# WaldoRevB.net
KiCad netlist of a schematic drawn in EAGLE
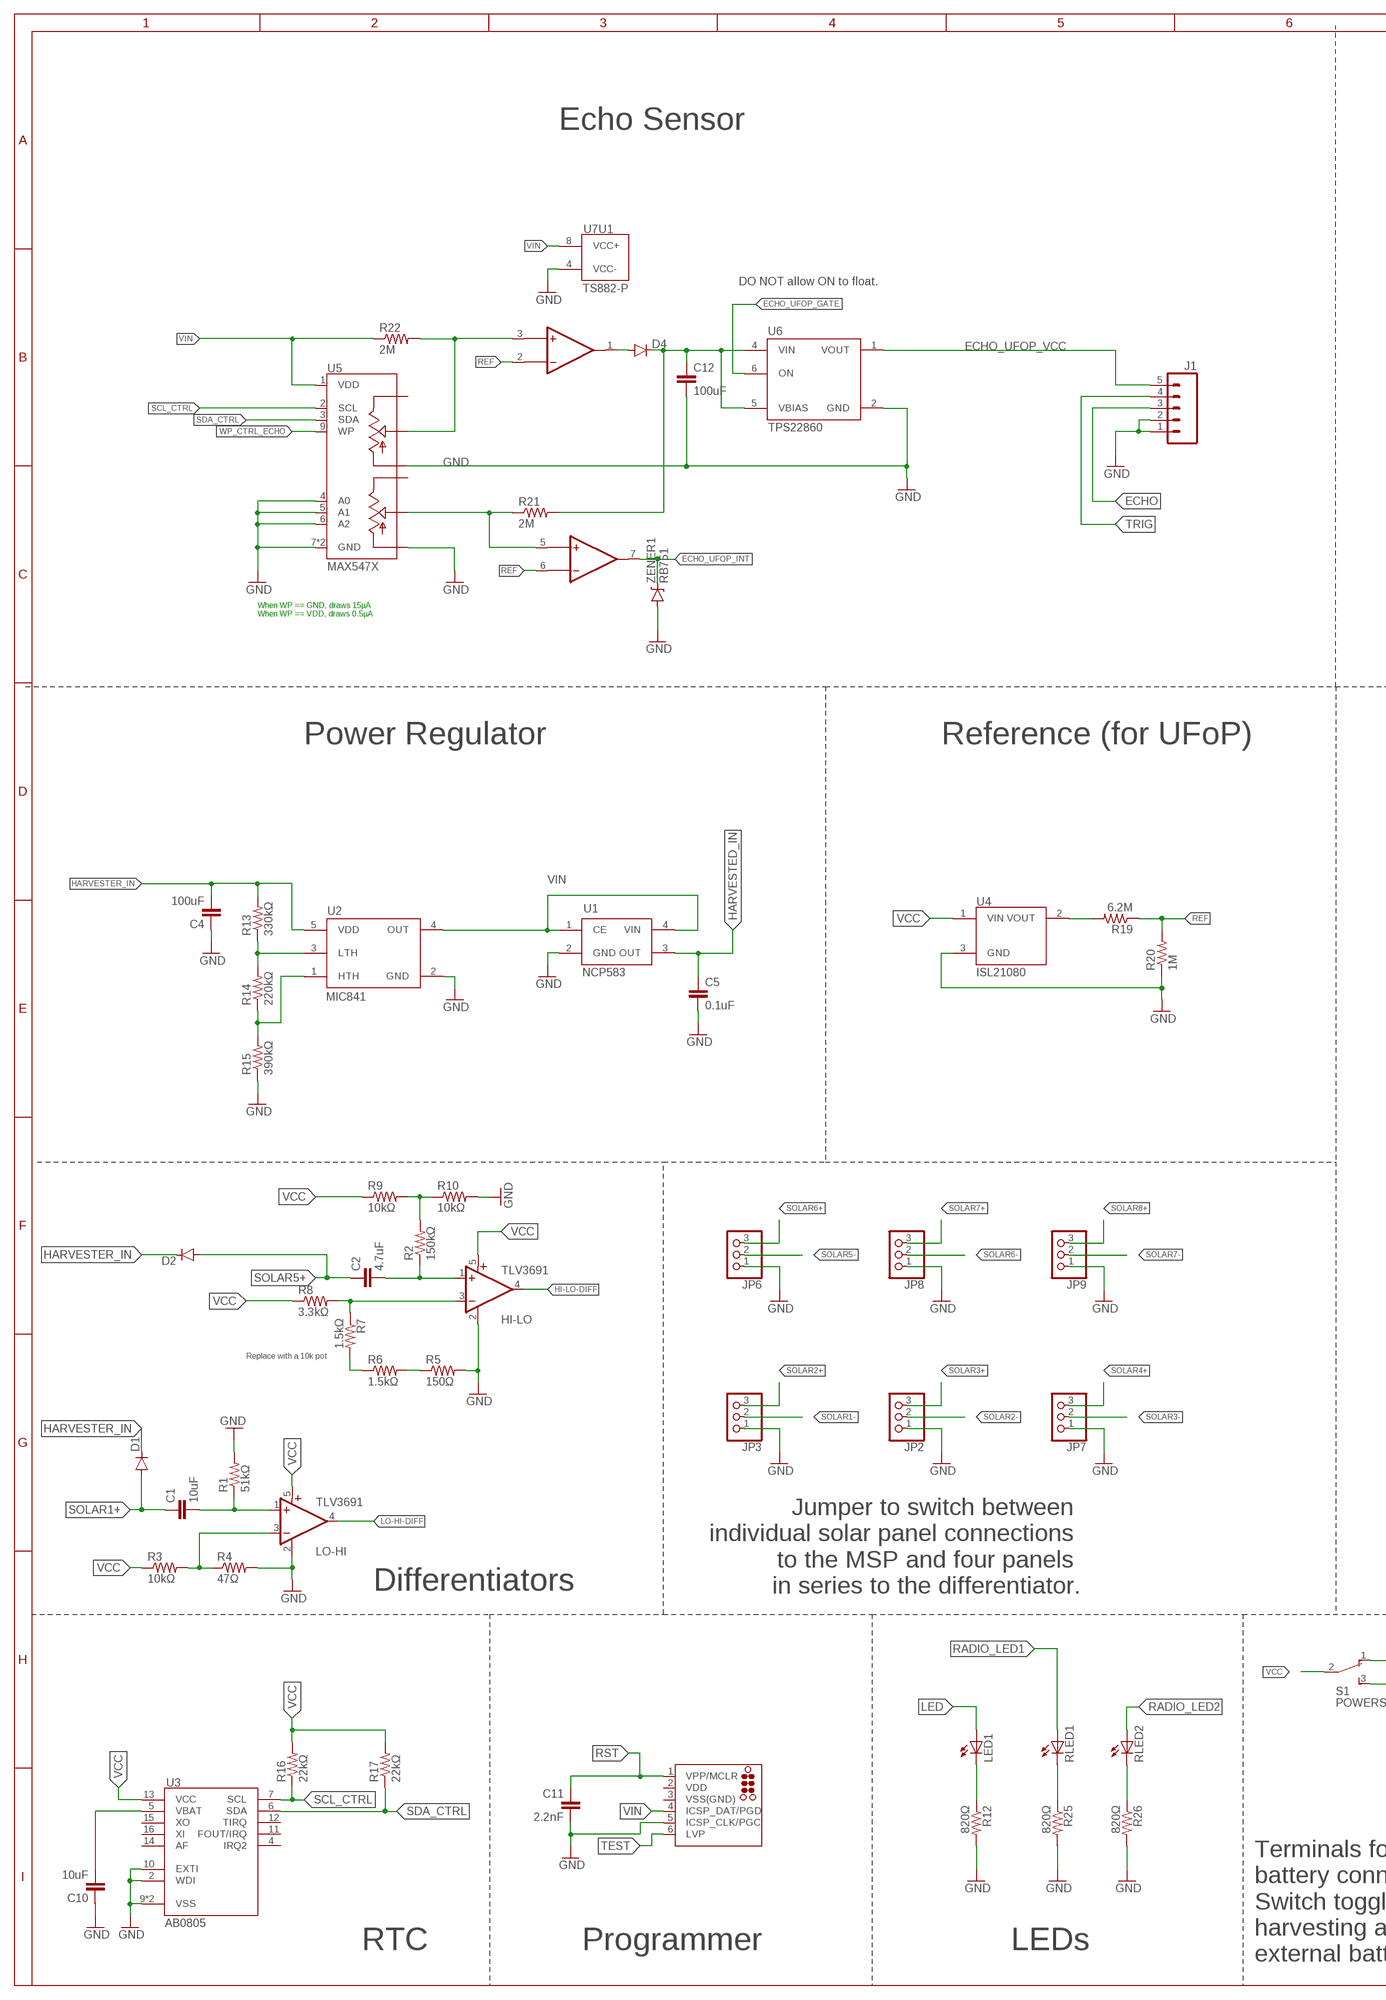
[diagram p0: schematic, sheet 1, part 1 of 2]
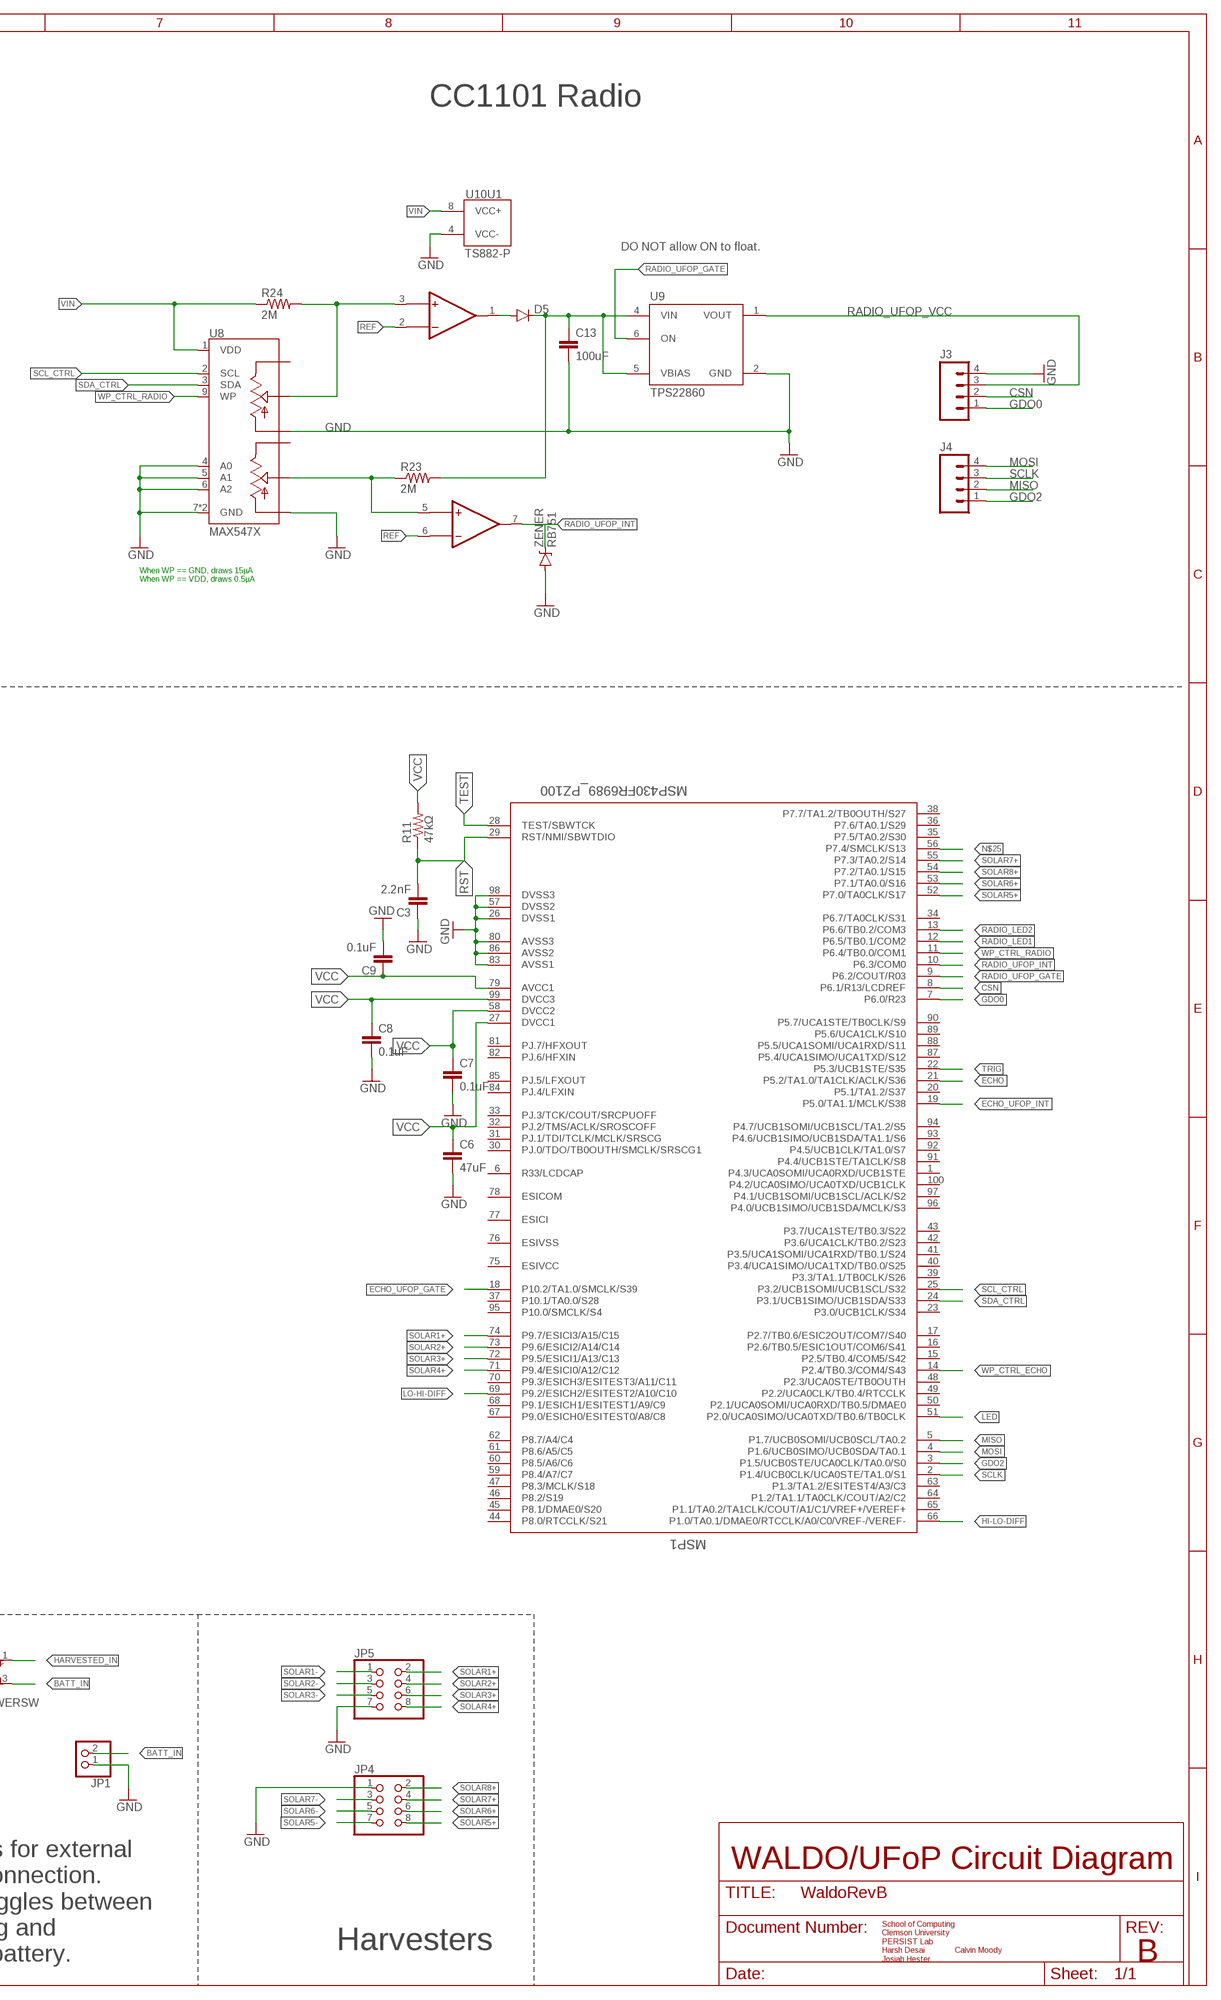
[diagram p1: schematic, sheet 1, part 2 of 2]

(export (version "E")
  (design (tool "Eeschema 10.0.6"))
  (components
    (comp (ref "C1")
      (value "10uF")
      (footprint "eagle-import:0805")
      (libsource (lib "eagle-import") (part "CAP0805"))
    )
    (comp (ref "C2")
      (value "4.7uF")
      (footprint "eagle-import:0805")
      (libsource (lib "eagle-import") (part "CAP0805"))
    )
    (comp (ref "C3")
      (value "2.2nF")
      (footprint "eagle-import:0805")
      (libsource (lib "eagle-import") (part "CAP0805"))
    )
    (comp (ref "C4")
      (value "100uF")
      (footprint "eagle-import:0805")
      (libsource (lib "eagle-import") (part "CAP0805"))
    )
    (comp (ref "C5")
      (value "0.1uF")
      (footprint "eagle-import:0805")
      (libsource (lib "eagle-import") (part "CAP0805"))
    )
    (comp (ref "C6")
      (value "47uF")
      (footprint "eagle-import:0805")
      (libsource (lib "eagle-import") (part "CAP0805"))
    )
    (comp (ref "C7")
      (value "0.1uF")
      (footprint "eagle-import:0805")
      (libsource (lib "eagle-import") (part "CAP0805"))
    )
    (comp (ref "C8")
      (value "0.1uF")
      (footprint "eagle-import:0805")
      (libsource (lib "eagle-import") (part "CAP0805"))
    )
    (comp (ref "C9")
      (value "0.1uF")
      (footprint "eagle-import:0805")
      (libsource (lib "eagle-import") (part "CAP0805"))
    )
    (comp (ref "C10")
      (value "10uF")
      (footprint "eagle-import:0805")
      (libsource (lib "eagle-import") (part "CAP0805"))
    )
    (comp (ref "C11")
      (value "2.2nF")
      (footprint "eagle-import:0805")
      (libsource (lib "eagle-import") (part "CAP0805"))
    )
    (comp (ref "C12")
      (value "100uF")
      (footprint "eagle-import:0805")
      (libsource (lib "eagle-import") (part "CAP0805"))
    )
    (comp (ref "C13")
      (value "100uF")
      (footprint "eagle-import:0805")
      (libsource (lib "eagle-import") (part "CAP0805"))
    )
    (comp (ref "D1")
      (value "DIODESOD523")
      (footprint "eagle-import:SOD523")
      (libsource (lib "eagle-import") (part "DIODESOD523"))
    )
    (comp (ref "D2")
      (value "DIODESOD523")
      (footprint "eagle-import:SOD523")
      (libsource (lib "eagle-import") (part "DIODESOD523"))
    )
    (comp (ref "D4")
      (value "DIODESOD523")
      (footprint "eagle-import:SOD523")
      (libsource (lib "eagle-import") (part "DIODESOD523"))
    )
    (comp (ref "D5")
      (value "DIODESOD523")
      (footprint "eagle-import:SOD523")
      (libsource (lib "eagle-import") (part "DIODESOD523"))
    )
    (comp (ref "HI-LO")
      (value "TLV3691")
      (footprint "eagle-import:SC70-5")
      (libsource (lib "eagle-import") (part "TLV3691"))
    )
    (comp (ref "J1")
      (value "M05PTH")
      (footprint "eagle-import:1X05")
      (libsource (lib "eagle-import") (part "M05PTH"))
    )
    (comp (ref "J2")
      (value "TC2030-MCP-NL")
      (footprint "eagle-import:TC2030-MCP-NL")
      (libsource (lib "eagle-import") (part "TC2030-MCP-NL"))
    )
    (comp (ref "J3")
      (value "M04PTH")
      (footprint "eagle-import:1X04")
      (libsource (lib "eagle-import") (part "M04PTH"))
    )
    (comp (ref "J4")
      (value "M04PTH")
      (footprint "eagle-import:1X04")
      (libsource (lib "eagle-import") (part "M04PTH"))
    )
    (comp (ref "JP1")
      (value "PINHD-1X2")
      (footprint "eagle-import:1X02")
      (libsource (lib "eagle-import") (part "PINHD-1X2"))
    )
    (comp (ref "JP2")
      (value "PINHD-1X3")
      (footprint "eagle-import:1X03")
      (libsource (lib "eagle-import") (part "PINHD-1X3"))
    )
    (comp (ref "JP3")
      (value "PINHD-1X3")
      (footprint "eagle-import:1X03")
      (libsource (lib "eagle-import") (part "PINHD-1X3"))
    )
    (comp (ref "JP4")
      (value "PINHD-2X4")
      (footprint "eagle-import:2X04")
      (libsource (lib "eagle-import") (part "PINHD-2X4"))
    )
    (comp (ref "JP5")
      (value "PINHD-2X4")
      (footprint "eagle-import:2X04")
      (libsource (lib "eagle-import") (part "PINHD-2X4"))
    )
    (comp (ref "JP6")
      (value "PINHD-1X3")
      (footprint "eagle-import:1X03")
      (libsource (lib "eagle-import") (part "PINHD-1X3"))
    )
    (comp (ref "JP7")
      (value "PINHD-1X3")
      (footprint "eagle-import:1X03")
      (libsource (lib "eagle-import") (part "PINHD-1X3"))
    )
    (comp (ref "JP8")
      (value "PINHD-1X3")
      (footprint "eagle-import:1X03")
      (libsource (lib "eagle-import") (part "PINHD-1X3"))
    )
    (comp (ref "JP9")
      (value "PINHD-1X3")
      (footprint "eagle-import:1X03")
      (libsource (lib "eagle-import") (part "PINHD-1X3"))
    )
    (comp (ref "LED1")
      (value "LEDCHIP-LED0805")
      (footprint "eagle-import:CHIP-LED0805")
      (libsource (lib "eagle-import") (part "LEDCHIP-LED0805"))
    )
    (comp (ref "LO-HI")
      (value "TLV3691")
      (footprint "eagle-import:SC70-5")
      (libsource (lib "eagle-import") (part "TLV3691"))
    )
    (comp (ref "MSP1")
      (value "MSP430FR6989_PZ100")
      (footprint "eagle-import:PZ100")
      (libsource (lib "eagle-import") (part "MSP430FR6989_PZ100"))
    )
    (comp (ref "R1")
      (value "51kΩ")
      (footprint "eagle-import:0805")
      (libsource (lib "eagle-import") (part "RESISTOR0805-RES"))
    )
    (comp (ref "R2")
      (value "150kΩ")
      (footprint "eagle-import:0805")
      (libsource (lib "eagle-import") (part "RESISTOR0805-RES"))
    )
    (comp (ref "R3")
      (value "10kΩ")
      (footprint "eagle-import:0805")
      (libsource (lib "eagle-import") (part "RESISTOR0805-RES"))
    )
    (comp (ref "R4")
      (value "47Ω")
      (footprint "eagle-import:0805")
      (libsource (lib "eagle-import") (part "RESISTOR0805-RES"))
    )
    (comp (ref "R5")
      (value "150Ω")
      (footprint "eagle-import:0805")
      (libsource (lib "eagle-import") (part "RESISTOR0805-RES"))
    )
    (comp (ref "R6")
      (value "1.5kΩ")
      (footprint "eagle-import:0805")
      (libsource (lib "eagle-import") (part "RESISTOR0805-RES"))
    )
    (comp (ref "R7")
      (value "1.5kΩ")
      (footprint "eagle-import:0805")
      (libsource (lib "eagle-import") (part "RESISTOR0805-RES"))
    )
    (comp (ref "R8")
      (value "3.3kΩ")
      (footprint "eagle-import:0805")
      (libsource (lib "eagle-import") (part "RESISTOR0805-RES"))
    )
    (comp (ref "R9")
      (value "10kΩ")
      (footprint "eagle-import:0805")
      (libsource (lib "eagle-import") (part "RESISTOR0805-RES"))
    )
    (comp (ref "R10")
      (value "10kΩ")
      (footprint "eagle-import:0805")
      (libsource (lib "eagle-import") (part "RESISTOR0805-RES"))
    )
    (comp (ref "R11")
      (value "47kΩ")
      (footprint "eagle-import:0805")
      (libsource (lib "eagle-import") (part "RESISTOR0805-RES"))
    )
    (comp (ref "R12")
      (value "820Ω")
      (footprint "eagle-import:0805")
      (libsource (lib "eagle-import") (part "RESISTOR0805-RES"))
    )
    (comp (ref "R13")
      (value "330kΩ")
      (footprint "eagle-import:0805")
      (libsource (lib "eagle-import") (part "RESISTOR0805-RES"))
    )
    (comp (ref "R14")
      (value "220kΩ")
      (footprint "eagle-import:0805")
      (libsource (lib "eagle-import") (part "RESISTOR0805-RES"))
    )
    (comp (ref "R15")
      (value "390kΩ")
      (footprint "eagle-import:0805")
      (libsource (lib "eagle-import") (part "RESISTOR0805-RES"))
    )
    (comp (ref "R16")
      (value "22kΩ")
      (footprint "eagle-import:0805")
      (libsource (lib "eagle-import") (part "RESISTOR0805-RES"))
    )
    (comp (ref "R17")
      (value "22kΩ")
      (footprint "eagle-import:0805")
      (libsource (lib "eagle-import") (part "RESISTOR0805-RES"))
    )
    (comp (ref "R19")
      (value "6.2M")
      (footprint "eagle-import:0805")
      (libsource (lib "eagle-import") (part "RESISTOR0805-RES"))
    )
    (comp (ref "R20")
      (value "1M")
      (footprint "eagle-import:0805")
      (libsource (lib "eagle-import") (part "RESISTOR0805-RES"))
    )
    (comp (ref "R21")
      (value "2M")
      (footprint "eagle-import:0805")
      (libsource (lib "eagle-import") (part "RESISTOR0805-RES"))
    )
    (comp (ref "R22")
      (value "2M")
      (footprint "eagle-import:0805")
      (libsource (lib "eagle-import") (part "RESISTOR0805-RES"))
    )
    (comp (ref "R23")
      (value "2M")
      (footprint "eagle-import:0805")
      (libsource (lib "eagle-import") (part "RESISTOR0805-RES"))
    )
    (comp (ref "R24")
      (value "2M")
      (footprint "eagle-import:0805")
      (libsource (lib "eagle-import") (part "RESISTOR0805-RES"))
    )
    (comp (ref "R25")
      (value "820Ω")
      (footprint "eagle-import:0805")
      (libsource (lib "eagle-import") (part "RESISTOR0805-RES"))
    )
    (comp (ref "R26")
      (value "820Ω")
      (footprint "eagle-import:0805")
      (libsource (lib "eagle-import") (part "RESISTOR0805-RES"))
    )
    (comp (ref "RLED1")
      (value "LEDCHIP-LED0805")
      (footprint "eagle-import:CHIP-LED0805")
      (libsource (lib "eagle-import") (part "LEDCHIP-LED0805"))
    )
    (comp (ref "RLED2")
      (value "LEDCHIP-LED0805")
      (footprint "eagle-import:CHIP-LED0805")
      (libsource (lib "eagle-import") (part "LEDCHIP-LED0805"))
    )
    (comp (ref "S1")
      (value "POWERSW")
      (footprint "eagle-import:TL3XYO")
      (libsource (lib "eagle-import") (part "POWERSW"))
    )
    (comp (ref "U1")
      (value "NCP583")
      (footprint "eagle-import:SC82-AB_1PRIMARY")
      (libsource (lib "eagle-import") (part "NCP583"))
    )
    (comp (ref "U2")
      (value "MIC841")
      (footprint "eagle-import:SC70-5")
      (libsource (lib "eagle-import") (part "MIC841"))
    )
    (comp (ref "U3")
      (value "AB0805")
      (footprint "eagle-import:QFN16")
      (libsource (lib "eagle-import") (part "AB0805"))
    )
    (comp (ref "U4")
      (value "ISL21080")
      (footprint "eagle-import:SOT-23")
      (libsource (lib "eagle-import") (part "ISL21080"))
    )
    (comp (ref "U5")
      (value "MAX547X")
      (footprint "eagle-import:QFN16")
      (libsource (lib "eagle-import") (part "MAX547X"))
    )
    (comp (ref "U6")
      (value "TPS22860")
      (footprint "eagle-import:TSOT23-6")
      (libsource (lib "eagle-import") (part "TPS22860"))
    )
    (comp (ref "U7")
      (value "TS882-P")
      (footprint "eagle-import:UDFN8")
      (fields (field (name "DIGIKEY") "497-14073-1-ND"))
      (libsource (lib "eagle-import") (part "TS882-P"))
    )
    (comp (ref "U8")
      (value "MAX547X")
      (footprint "eagle-import:QFN16")
      (libsource (lib "eagle-import") (part "MAX547X"))
    )
    (comp (ref "U9")
      (value "TPS22860")
      (footprint "eagle-import:TSOT23-6")
      (libsource (lib "eagle-import") (part "TPS22860"))
    )
    (comp (ref "U10")
      (value "TS882-P")
      (footprint "eagle-import:UDFN8")
      (fields (field (name "DIGIKEY") "497-14073-1-ND"))
      (libsource (lib "eagle-import") (part "TS882-P"))
    )
    (comp (ref "ZENER")
      (value "RB751")
      (footprint "eagle-import:SOD-523")
      (libsource (lib "eagle-import") (part "DIODE-ZENER"))
    )
    (comp (ref "ZENER1")
      (value "RB751")
      (footprint "eagle-import:SOD-523")
      (libsource (lib "eagle-import") (part "DIODE-ZENER"))
    )
  )
  (nets
    (net (code "1") (name "/ECHO_UFOP_VCC") (class "Default")
      (node (ref "J1") (pin "5") (pinfunction "5_5") (pintype "passive"))
      (node (ref "U6") (pin "1") (pinfunction "VOUT_1") (pintype "bidirectional"))
    )
    (net (code "2") (name "/RADIO_UFOP_VCC") (class "Default")
      (node (ref "J3") (pin "3") (pinfunction "3_3") (pintype "passive"))
      (node (ref "U9") (pin "1") (pinfunction "VOUT_1") (pintype "bidirectional"))
    )
    (net (code "3") (name "/VDD") (class "Default")
      (node (ref "J2") (pin "2") (pinfunction "VDD_2") (pintype "power_in"))
    )
    (net (code "4") (name "/VSS(GND)") (class "Default")
      (node (ref "J2") (pin "3") (pinfunction "VSS(GND)_3") (pintype "power_in"))
    )
    (net (code "5") (name "BATT_IN") (class "Default")
      (node (ref "JP1") (pin "2") (pinfunction "2_2") (pintype "passive"))
      (node (ref "S1") (pin "3") (pinfunction "S_3") (pintype "passive"))
    )
    (net (code "6") (name "CSN") (class "Default")
      (node (ref "J3") (pin "2") (pinfunction "2_2") (pintype "passive"))
      (node (ref "MSP1") (pin "8") (pinfunction "P6.1/R13/LCDREF_8") (pintype "bidirectional"))
    )
    (net (code "7") (name "ECHO") (class "Default")
      (node (ref "J1") (pin "3") (pinfunction "3_3") (pintype "passive"))
      (node (ref "MSP1") (pin "21") (pinfunction "P5.2/TA1.0/TA1CLK/ACLK/S36_21") (pintype "bidirectional"))
    )
    (net (code "8") (name "ECHO_UFOP_GATE") (class "Default")
      (node (ref "MSP1") (pin "18") (pinfunction "P10.2/TA1.0/SMCLK/S39_18") (pintype "bidirectional"))
      (node (ref "U6") (pin "6") (pinfunction "ON_6") (pintype "bidirectional"))
    )
    (net (code "9") (name "ECHO_UFOP_INT") (class "Default")
      (node (ref "MSP1") (pin "19") (pinfunction "P5.0/TA1.1/MCLK/S38_19") (pintype "bidirectional"))
      (node (ref "U7") (pin "7") (pinfunction "OUT1_7") (pintype "output"))
      (node (ref "ZENER1") (pin "CATHODE") (pinfunction "C_CATHODE") (pintype "passive"))
    )
    (net (code "10") (name "GDO0") (class "Default")
      (node (ref "J3") (pin "1") (pinfunction "1_1") (pintype "passive"))
      (node (ref "MSP1") (pin "7") (pinfunction "P6.0/R23_7") (pintype "bidirectional"))
    )
    (net (code "11") (name "GDO2") (class "Default")
      (node (ref "J4") (pin "1") (pinfunction "1_1") (pintype "passive"))
      (node (ref "MSP1") (pin "3") (pinfunction "P1.5/UCB0STE/UCA0CLK/TA0.0/S0_3") (pintype "bidirectional"))
    )
    (net (code "12") (name "GND") (class "Default")
      (node (ref "C10") (pin "1") (pinfunction "1_1") (pintype "passive"))
      (node (ref "C11") (pin "2") (pinfunction "2_2") (pintype "passive"))
      (node (ref "C12") (pin "2") (pinfunction "2_2") (pintype "passive"))
      (node (ref "C13") (pin "2") (pinfunction "2_2") (pintype "passive"))
      (node (ref "C3") (pin "1") (pinfunction "1_1") (pintype "passive"))
      (node (ref "C4") (pin "1") (pinfunction "1_1") (pintype "passive"))
      (node (ref "C5") (pin "2") (pinfunction "2_2") (pintype "passive"))
      (node (ref "C6") (pin "2") (pinfunction "2_2") (pintype "passive"))
      (node (ref "C7") (pin "2") (pinfunction "2_2") (pintype "passive"))
      (node (ref "C8") (pin "2") (pinfunction "2_2") (pintype "passive"))
      (node (ref "C9") (pin "2") (pinfunction "2_2") (pintype "passive"))
      (node (ref "HI-LO") (pin "2") (pinfunction "GND_2") (pintype "power_in"))
      (node (ref "J1") (pin "1") (pinfunction "1_1") (pintype "passive"))
      (node (ref "J1") (pin "2") (pinfunction "2_2") (pintype "passive"))
      (node (ref "J2") (pin "5") (pinfunction "ICSP_CLK/PGC_5") (pintype "output"))
      (node (ref "J3") (pin "4") (pinfunction "4_4") (pintype "passive"))
      (node (ref "JP1") (pin "1") (pinfunction "1_1") (pintype "passive"))
      (node (ref "JP2") (pin "1") (pinfunction "1_1") (pintype "passive"))
      (node (ref "JP3") (pin "1") (pinfunction "1_1") (pintype "passive"))
      (node (ref "JP4") (pin "1") (pinfunction "1_1") (pintype "passive"))
      (node (ref "JP5") (pin "7") (pinfunction "7_7") (pintype "passive"))
      (node (ref "JP6") (pin "1") (pinfunction "1_1") (pintype "passive"))
      (node (ref "JP7") (pin "1") (pinfunction "1_1") (pintype "passive"))
      (node (ref "JP8") (pin "1") (pinfunction "1_1") (pintype "passive"))
      (node (ref "JP9") (pin "1") (pinfunction "1_1") (pintype "passive"))
      (node (ref "LO-HI") (pin "2") (pinfunction "GND_2") (pintype "power_in"))
      (node (ref "MSP1") (pin "26") (pinfunction "DVSS1_26") (pintype "bidirectional"))
      (node (ref "MSP1") (pin "57") (pinfunction "DVSS2_57") (pintype "bidirectional"))
      (node (ref "MSP1") (pin "80") (pinfunction "AVSS3_80") (pintype "bidirectional"))
      (node (ref "MSP1") (pin "83") (pinfunction "AVSS1_83") (pintype "bidirectional"))
      (node (ref "MSP1") (pin "86") (pinfunction "AVSS2_86") (pintype "bidirectional"))
      (node (ref "MSP1") (pin "98") (pinfunction "DVSS3_98") (pintype "bidirectional"))
      (node (ref "R1") (pin "2") (pinfunction "2_2") (pintype "passive"))
      (node (ref "R10") (pin "2") (pinfunction "2_2") (pintype "passive"))
      (node (ref "R12") (pin "2") (pinfunction "2_2") (pintype "passive"))
      (node (ref "R15") (pin "1") (pinfunction "1_1") (pintype "passive"))
      (node (ref "R20") (pin "1") (pinfunction "1_1") (pintype "passive"))
      (node (ref "R25") (pin "2") (pinfunction "2_2") (pintype "passive"))
      (node (ref "R26") (pin "2") (pinfunction "2_2") (pintype "passive"))
      (node (ref "R4") (pin "2") (pinfunction "2_2") (pintype "passive"))
      (node (ref "R5") (pin "2") (pinfunction "2_2") (pintype "passive"))
      (node (ref "U1") (pin "2") (pinfunction "GND_2") (pintype "bidirectional"))
      (node (ref "U10") (pin "4") (pinfunction "VCC-_4") (pintype "bidirectional"))
      (node (ref "U2") (pin "2") (pinfunction "GND_2") (pintype "bidirectional"))
      (node (ref "U3") (pin "10") (pinfunction "EXTI_10") (pintype "bidirectional"))
      (node (ref "U3") (pin "2") (pinfunction "WDI_2") (pintype "bidirectional"))
      (node (ref "U3") (pin "9") (pinfunction "VSS_9") (pintype "bidirectional"))
      (node (ref "U3") (pin "TH") (pinfunction "VSS_TH") (pintype "bidirectional"))
      (node (ref "U4") (pin "3") (pinfunction "GND_3") (pintype "bidirectional"))
      (node (ref "U5") (pin "10") (pinfunction "LB_10") (pintype "bidirectional"))
      (node (ref "U5") (pin "13") (pinfunction "LA_13") (pintype "passive"))
      (node (ref "U5") (pin "4") (pinfunction "A0_4") (pintype "bidirectional"))
      (node (ref "U5") (pin "5") (pinfunction "A1_5") (pintype "bidirectional"))
      (node (ref "U5") (pin "6") (pinfunction "A2_6") (pintype "bidirectional"))
      (node (ref "U5") (pin "7") (pinfunction "GND_7") (pintype "bidirectional"))
      (node (ref "U5") (pin "TH") (pinfunction "GND_TH") (pintype "bidirectional"))
      (node (ref "U6") (pin "2") (pinfunction "GND_2") (pintype "bidirectional"))
      (node (ref "U7") (pin "4") (pinfunction "VCC-_4") (pintype "bidirectional"))
      (node (ref "U8") (pin "10") (pinfunction "LB_10") (pintype "bidirectional"))
      (node (ref "U8") (pin "13") (pinfunction "LA_13") (pintype "passive"))
      (node (ref "U8") (pin "4") (pinfunction "A0_4") (pintype "bidirectional"))
      (node (ref "U8") (pin "5") (pinfunction "A1_5") (pintype "bidirectional"))
      (node (ref "U8") (pin "6") (pinfunction "A2_6") (pintype "bidirectional"))
      (node (ref "U8") (pin "7") (pinfunction "GND_7") (pintype "bidirectional"))
      (node (ref "U8") (pin "TH") (pinfunction "GND_TH") (pintype "bidirectional"))
      (node (ref "U9") (pin "2") (pinfunction "GND_2") (pintype "bidirectional"))
      (node (ref "ZENER") (pin "ANODE") (pinfunction "A_ANODE") (pintype "passive"))
      (node (ref "ZENER1") (pin "ANODE") (pinfunction "A_ANODE") (pintype "passive"))
    )
    (net (code "13") (name "HARVESTED_IN") (class "Default")
      (node (ref "C5") (pin "1") (pinfunction "1_1") (pintype "passive"))
      (node (ref "S1") (pin "1") (pinfunction "O_1") (pintype "passive"))
      (node (ref "U1") (pin "3") (pinfunction "OUT_3") (pintype "bidirectional"))
    )
    (net (code "14") (name "HARVESTER_IN") (class "Default")
      (node (ref "C4") (pin "2") (pinfunction "2_2") (pintype "passive"))
      (node (ref "D1") (pin "C") (pinfunction "C_C") (pintype "passive"))
      (node (ref "D2") (pin "C") (pinfunction "C_C") (pintype "passive"))
      (node (ref "R13") (pin "2") (pinfunction "2_2") (pintype "passive"))
      (node (ref "U2") (pin "5") (pinfunction "VDD_5") (pintype "bidirectional"))
    )
    (net (code "15") (name "HI-LO-DIFF") (class "Default")
      (node (ref "HI-LO") (pin "4") (pinfunction "OUT_4") (pintype "output"))
      (node (ref "MSP1") (pin "66") (pinfunction "P1.0/TA0.1/DMAE0/RTCCLK/A0/C0/VREF-/VEREF-_66") (pintype "bidirectional"))
    )
    (net (code "16") (name "LED") (class "Default")
      (node (ref "LED1") (pin "A") (pinfunction "A_A") (pintype "passive"))
      (node (ref "MSP1") (pin "51") (pinfunction "P2.0/UCA0SIMO/UCA0TXD/TB0.6/TB0CLK_51") (pintype "bidirectional"))
    )
    (net (code "17") (name "LO-HI-DIFF") (class "Default")
      (node (ref "LO-HI") (pin "4") (pinfunction "OUT_4") (pintype "output"))
      (node (ref "MSP1") (pin "69") (pinfunction "P9.2/ESICH2/ESITEST2/A10/C10_69") (pintype "bidirectional"))
    )
    (net (code "18") (name "MISO") (class "Default")
      (node (ref "J4") (pin "2") (pinfunction "2_2") (pintype "passive"))
      (node (ref "MSP1") (pin "5") (pinfunction "P1.7/UCB0SOMI/UCB0SCL/TA0.2_5") (pintype "bidirectional"))
    )
    (net (code "19") (name "MOSI") (class "Default")
      (node (ref "J4") (pin "4") (pinfunction "4_4") (pintype "passive"))
      (node (ref "MSP1") (pin "4") (pinfunction "P1.6/UCB0SIMO/UCB0SDA/TA0.1_4") (pintype "bidirectional"))
    )
    (net (code "20") (name "N$25") (class "Default")
      (node (ref "MSP1") (pin "56") (pinfunction "P7.4/SMCLK/S13_56") (pintype "bidirectional"))
    )
    (net (code "21") (name "Net-(HI-LO-+IN)") (class "Default")
      (node (ref "C2") (pin "2") (pinfunction "2_2") (pintype "passive"))
      (node (ref "HI-LO") (pin "1") (pinfunction "+IN_1") (pintype "input"))
      (node (ref "R2") (pin "1") (pinfunction "1_1") (pintype "passive"))
    )
    (net (code "22") (name "Net-(HI-LO--IN)") (class "Default")
      (node (ref "HI-LO") (pin "3") (pinfunction "-IN_3") (pintype "input"))
      (node (ref "R7") (pin "1") (pinfunction "1_1") (pintype "passive"))
      (node (ref "R8") (pin "2") (pinfunction "2_2") (pintype "passive"))
    )
    (net (code "23") (name "Net-(LED1-PadC)") (class "Default")
      (node (ref "LED1") (pin "C") (pinfunction "C_C") (pintype "passive"))
      (node (ref "R12") (pin "1") (pinfunction "1_1") (pintype "passive"))
    )
    (net (code "24") (name "Net-(LO-HI-+IN)") (class "Default")
      (node (ref "C1") (pin "2") (pinfunction "2_2") (pintype "passive"))
      (node (ref "LO-HI") (pin "1") (pinfunction "+IN_1") (pintype "input"))
      (node (ref "R1") (pin "1") (pinfunction "1_1") (pintype "passive"))
    )
    (net (code "25") (name "Net-(LO-HI--IN)") (class "Default")
      (node (ref "LO-HI") (pin "3") (pinfunction "-IN_3") (pintype "input"))
      (node (ref "R3") (pin "2") (pinfunction "2_2") (pintype "passive"))
      (node (ref "R4") (pin "1") (pinfunction "1_1") (pintype "passive"))
    )
    (net (code "26") (name "Net-(R5-Pad1)") (class "Default")
      (node (ref "R5") (pin "1") (pinfunction "1_1") (pintype "passive"))
      (node (ref "R6") (pin "2") (pinfunction "2_2") (pintype "passive"))
    )
    (net (code "27") (name "Net-(R6-Pad1)") (class "Default")
      (node (ref "R6") (pin "1") (pinfunction "1_1") (pintype "passive"))
      (node (ref "R7") (pin "2") (pinfunction "2_2") (pintype "passive"))
    )
    (net (code "28") (name "Net-(R10-Pad1)") (class "Default")
      (node (ref "R10") (pin "1") (pinfunction "1_1") (pintype "passive"))
      (node (ref "R2") (pin "2") (pinfunction "2_2") (pintype "passive"))
      (node (ref "R9") (pin "2") (pinfunction "2_2") (pintype "passive"))
    )
    (net (code "29") (name "Net-(R25-Pad1)") (class "Default")
      (node (ref "R25") (pin "1") (pinfunction "1_1") (pintype "passive"))
      (node (ref "RLED1") (pin "C") (pinfunction "C_C") (pintype "passive"))
    )
    (net (code "30") (name "Net-(R26-Pad1)") (class "Default")
      (node (ref "R26") (pin "1") (pinfunction "1_1") (pintype "passive"))
      (node (ref "RLED2") (pin "C") (pinfunction "C_C") (pintype "passive"))
    )
    (net (code "31") (name "Net-(U2-HTH)") (class "Default")
      (node (ref "R14") (pin "1") (pinfunction "1_1") (pintype "passive"))
      (node (ref "R15") (pin "2") (pinfunction "2_2") (pintype "passive"))
      (node (ref "U2") (pin "1") (pinfunction "HTH_1") (pintype "bidirectional"))
    )
    (net (code "32") (name "Net-(U2-LTH)") (class "Default")
      (node (ref "R13") (pin "1") (pinfunction "1_1") (pintype "passive"))
      (node (ref "R14") (pin "2") (pinfunction "2_2") (pintype "passive"))
      (node (ref "U2") (pin "3") (pinfunction "LTH_3") (pintype "bidirectional"))
    )
    (net (code "33") (name "Net-(U3-VBAT)") (class "Default")
      (node (ref "C10") (pin "2") (pinfunction "2_2") (pintype "passive"))
      (node (ref "U3") (pin "5") (pinfunction "VBAT_5") (pintype "bidirectional"))
    )
    (net (code "34") (name "Net-(U4-VOUT)") (class "Default")
      (node (ref "R19") (pin "2") (pinfunction "2_2") (pintype "passive"))
      (node (ref "U4") (pin "2") (pinfunction "VOUT_2") (pintype "bidirectional"))
    )
    (net (code "35") (name "Net-(U5-WA)") (class "Default")
      (node (ref "R22") (pin "2") (pinfunction "2_2") (pintype "passive"))
      (node (ref "U5") (pin "14") (pinfunction "WA_14") (pintype "passive"))
      (node (ref "U7") (pin "3") (pinfunction "IN1+_3") (pintype "input"))
    )
    (net (code "36") (name "Net-(U5-WB)") (class "Default")
      (node (ref "R21") (pin "1") (pinfunction "1_1") (pintype "passive"))
      (node (ref "U5") (pin "11") (pinfunction "WB_11") (pintype "bidirectional"))
      (node (ref "U7") (pin "5") (pinfunction "IN1+_5") (pintype "input"))
    )
    (net (code "37") (name "Net-(U6-VBIAS)") (class "Default")
      (node (ref "C12") (pin "1") (pinfunction "1_1") (pintype "passive"))
      (node (ref "D4") (pin "C") (pinfunction "C_C") (pintype "passive"))
      (node (ref "R21") (pin "2") (pinfunction "2_2") (pintype "passive"))
      (node (ref "U6") (pin "4") (pinfunction "VIN_4") (pintype "bidirectional"))
      (node (ref "U6") (pin "5") (pinfunction "VBIAS_5") (pintype "bidirectional"))
    )
    (net (code "38") (name "Net-(U7A-OUT1)") (class "Default")
      (node (ref "D4") (pin "A") (pinfunction "A_A") (pintype "passive"))
      (node (ref "U7") (pin "1") (pinfunction "OUT1_1") (pintype "output"))
    )
    (net (code "39") (name "Net-(U9-VBIAS)") (class "Default")
      (node (ref "C13") (pin "1") (pinfunction "1_1") (pintype "passive"))
      (node (ref "D5") (pin "C") (pinfunction "C_C") (pintype "passive"))
      (node (ref "R23") (pin "2") (pinfunction "2_2") (pintype "passive"))
      (node (ref "U9") (pin "4") (pinfunction "VIN_4") (pintype "bidirectional"))
      (node (ref "U9") (pin "5") (pinfunction "VBIAS_5") (pintype "bidirectional"))
    )
    (net (code "40") (name "Net-(U10A-IN1+)") (class "Default")
      (node (ref "R24") (pin "2") (pinfunction "2_2") (pintype "passive"))
      (node (ref "U10") (pin "3") (pinfunction "IN1+_3") (pintype "input"))
      (node (ref "U8") (pin "14") (pinfunction "WA_14") (pintype "passive"))
    )
    (net (code "41") (name "Net-(U10A-OUT1)") (class "Default")
      (node (ref "D5") (pin "A") (pinfunction "A_A") (pintype "passive"))
      (node (ref "U10") (pin "1") (pinfunction "OUT1_1") (pintype "output"))
    )
    (net (code "42") (name "Net-(U10B-IN1+)") (class "Default")
      (node (ref "R23") (pin "1") (pinfunction "1_1") (pintype "passive"))
      (node (ref "U10") (pin "5") (pinfunction "IN1+_5") (pintype "input"))
      (node (ref "U8") (pin "11") (pinfunction "WB_11") (pintype "bidirectional"))
    )
    (net (code "43") (name "RADIO_LED1") (class "Default")
      (node (ref "MSP1") (pin "12") (pinfunction "P6.5/TB0.1/COM2_12") (pintype "bidirectional"))
      (node (ref "RLED1") (pin "A") (pinfunction "A_A") (pintype "passive"))
    )
    (net (code "44") (name "RADIO_LED2") (class "Default")
      (node (ref "MSP1") (pin "13") (pinfunction "P6.6/TB0.2/COM3_13") (pintype "bidirectional"))
      (node (ref "RLED2") (pin "A") (pinfunction "A_A") (pintype "passive"))
    )
    (net (code "45") (name "RADIO_UFOP_GATE") (class "Default")
      (node (ref "MSP1") (pin "9") (pinfunction "P6.2/COUT/R03_9") (pintype "bidirectional"))
      (node (ref "U9") (pin "6") (pinfunction "ON_6") (pintype "bidirectional"))
    )
    (net (code "46") (name "RADIO_UFOP_INT") (class "Default")
      (node (ref "MSP1") (pin "10") (pinfunction "P6.3/COM0_10") (pintype "bidirectional"))
      (node (ref "U10") (pin "7") (pinfunction "OUT1_7") (pintype "output"))
      (node (ref "ZENER") (pin "CATHODE") (pinfunction "C_CATHODE") (pintype "passive"))
    )
    (net (code "47") (name "REF") (class "Default")
      (node (ref "R19") (pin "1") (pinfunction "1_1") (pintype "passive"))
      (node (ref "R20") (pin "2") (pinfunction "2_2") (pintype "passive"))
      (node (ref "U10") (pin "2") (pinfunction "IN1-_2") (pintype "input"))
      (node (ref "U10") (pin "6") (pinfunction "IN1-_6") (pintype "input"))
      (node (ref "U7") (pin "2") (pinfunction "IN1-_2") (pintype "input"))
      (node (ref "U7") (pin "6") (pinfunction "IN1-_6") (pintype "input"))
    )
    (net (code "48") (name "RST") (class "Default")
      (node (ref "C11") (pin "1") (pinfunction "1_1") (pintype "passive"))
      (node (ref "C3") (pin "2") (pinfunction "2_2") (pintype "passive"))
      (node (ref "J2") (pin "1") (pinfunction "VPP/MCLR_1") (pintype "passive"))
      (node (ref "MSP1") (pin "29") (pinfunction "RST/NMI/SBWTDIO_29") (pintype "bidirectional"))
      (node (ref "R11") (pin "1") (pinfunction "1_1") (pintype "passive"))
    )
    (net (code "49") (name "SCLK") (class "Default")
      (node (ref "J4") (pin "3") (pinfunction "3_3") (pintype "passive"))
      (node (ref "MSP1") (pin "2") (pinfunction "P1.4/UCB0CLK/UCA0STE/TA1.0/S1_2") (pintype "bidirectional"))
    )
    (net (code "50") (name "SCL_CTRL") (class "Default")
      (node (ref "MSP1") (pin "25") (pinfunction "P3.2/UCB1SOMI/UCB1SCL/S32_25") (pintype "bidirectional"))
      (node (ref "R16") (pin "1") (pinfunction "1_1") (pintype "passive"))
      (node (ref "U3") (pin "7") (pinfunction "SCL_7") (pintype "bidirectional"))
      (node (ref "U5") (pin "2") (pinfunction "SCL_2") (pintype "bidirectional"))
      (node (ref "U8") (pin "2") (pinfunction "SCL_2") (pintype "bidirectional"))
    )
    (net (code "51") (name "SDA_CTRL") (class "Default")
      (node (ref "MSP1") (pin "24") (pinfunction "P3.1/UCB1SIMO/UCB1SDA/S33_24") (pintype "bidirectional"))
      (node (ref "R17") (pin "1") (pinfunction "1_1") (pintype "passive"))
      (node (ref "U3") (pin "6") (pinfunction "SDA_6") (pintype "bidirectional"))
      (node (ref "U5") (pin "3") (pinfunction "SDA_3") (pintype "bidirectional"))
      (node (ref "U8") (pin "3") (pinfunction "SDA_3") (pintype "bidirectional"))
    )
    (net (code "52") (name "SOLAR1+") (class "Default")
      (node (ref "C1") (pin "1") (pinfunction "1_1") (pintype "passive"))
      (node (ref "D1") (pin "A") (pinfunction "A_A") (pintype "passive"))
      (node (ref "JP5") (pin "2") (pinfunction "2_2") (pintype "passive"))
      (node (ref "MSP1") (pin "74") (pinfunction "P9.7/ESICI3/A15/C15_74") (pintype "bidirectional"))
    )
    (net (code "53") (name "SOLAR1-") (class "Default")
      (node (ref "JP3") (pin "2") (pinfunction "2_2") (pintype "passive"))
      (node (ref "JP5") (pin "1") (pinfunction "1_1") (pintype "passive"))
    )
    (net (code "54") (name "SOLAR2+") (class "Default")
      (node (ref "JP3") (pin "3") (pinfunction "3_3") (pintype "passive"))
      (node (ref "JP5") (pin "4") (pinfunction "4_4") (pintype "passive"))
      (node (ref "MSP1") (pin "73") (pinfunction "P9.6/ESICI2/A14/C14_73") (pintype "bidirectional"))
    )
    (net (code "55") (name "SOLAR2-") (class "Default")
      (node (ref "JP2") (pin "2") (pinfunction "2_2") (pintype "passive"))
      (node (ref "JP5") (pin "3") (pinfunction "3_3") (pintype "passive"))
    )
    (net (code "56") (name "SOLAR3+") (class "Default")
      (node (ref "JP2") (pin "3") (pinfunction "3_3") (pintype "passive"))
      (node (ref "JP5") (pin "6") (pinfunction "6_6") (pintype "passive"))
      (node (ref "MSP1") (pin "72") (pinfunction "P9.5/ESICI1/A13/C13_72") (pintype "bidirectional"))
    )
    (net (code "57") (name "SOLAR3-") (class "Default")
      (node (ref "JP5") (pin "5") (pinfunction "5_5") (pintype "passive"))
      (node (ref "JP7") (pin "2") (pinfunction "2_2") (pintype "passive"))
    )
    (net (code "58") (name "SOLAR4+") (class "Default")
      (node (ref "JP5") (pin "8") (pinfunction "8_8") (pintype "passive"))
      (node (ref "JP7") (pin "3") (pinfunction "3_3") (pintype "passive"))
      (node (ref "MSP1") (pin "71") (pinfunction "P9.4/ESICI0/A12/C12_71") (pintype "bidirectional"))
    )
    (net (code "59") (name "SOLAR5+") (class "Default")
      (node (ref "C2") (pin "1") (pinfunction "1_1") (pintype "passive"))
      (node (ref "D2") (pin "A") (pinfunction "A_A") (pintype "passive"))
      (node (ref "JP4") (pin "8") (pinfunction "8_8") (pintype "passive"))
      (node (ref "MSP1") (pin "52") (pinfunction "P7.0/TA0CLK/S17_52") (pintype "bidirectional"))
    )
    (net (code "60") (name "SOLAR5-") (class "Default")
      (node (ref "JP4") (pin "7") (pinfunction "7_7") (pintype "passive"))
      (node (ref "JP6") (pin "2") (pinfunction "2_2") (pintype "passive"))
    )
    (net (code "61") (name "SOLAR6+") (class "Default")
      (node (ref "JP4") (pin "6") (pinfunction "6_6") (pintype "passive"))
      (node (ref "JP6") (pin "3") (pinfunction "3_3") (pintype "passive"))
      (node (ref "MSP1") (pin "53") (pinfunction "P7.1/TA0.0/S16_53") (pintype "bidirectional"))
    )
    (net (code "62") (name "SOLAR6-") (class "Default")
      (node (ref "JP4") (pin "5") (pinfunction "5_5") (pintype "passive"))
      (node (ref "JP8") (pin "2") (pinfunction "2_2") (pintype "passive"))
    )
    (net (code "63") (name "SOLAR7+") (class "Default")
      (node (ref "JP4") (pin "4") (pinfunction "4_4") (pintype "passive"))
      (node (ref "JP8") (pin "3") (pinfunction "3_3") (pintype "passive"))
      (node (ref "MSP1") (pin "55") (pinfunction "P7.3/TA0.2/S14_55") (pintype "bidirectional"))
    )
    (net (code "64") (name "SOLAR7-") (class "Default")
      (node (ref "JP4") (pin "3") (pinfunction "3_3") (pintype "passive"))
      (node (ref "JP9") (pin "2") (pinfunction "2_2") (pintype "passive"))
    )
    (net (code "65") (name "SOLAR8+") (class "Default")
      (node (ref "JP4") (pin "2") (pinfunction "2_2") (pintype "passive"))
      (node (ref "JP9") (pin "3") (pinfunction "3_3") (pintype "passive"))
      (node (ref "MSP1") (pin "54") (pinfunction "P7.2/TA0.1/S15_54") (pintype "bidirectional"))
    )
    (net (code "66") (name "TEST") (class "Default")
      (node (ref "J2") (pin "6") (pinfunction "LVP_6") (pintype "bidirectional"))
      (node (ref "MSP1") (pin "28") (pinfunction "TEST/SBWTCK_28") (pintype "bidirectional"))
    )
    (net (code "67") (name "TRIG") (class "Default")
      (node (ref "J1") (pin "4") (pinfunction "4_4") (pintype "passive"))
      (node (ref "MSP1") (pin "22") (pinfunction "P5.3/UCB1STE/S35_22") (pintype "bidirectional"))
    )
    (net (code "68") (name "VCC") (class "Default")
      (node (ref "C6") (pin "1") (pinfunction "1_1") (pintype "passive"))
      (node (ref "C7") (pin "1") (pinfunction "1_1") (pintype "passive"))
      (node (ref "C8") (pin "1") (pinfunction "1_1") (pintype "passive"))
      (node (ref "C9") (pin "1") (pinfunction "1_1") (pintype "passive"))
      (node (ref "HI-LO") (pin "5") (pinfunction "V+_5") (pintype "power_in"))
      (node (ref "LO-HI") (pin "5") (pinfunction "V+_5") (pintype "power_in"))
      (node (ref "MSP1") (pin "27") (pinfunction "DVCC1_27") (pintype "bidirectional"))
      (node (ref "MSP1") (pin "58") (pinfunction "DVCC2_58") (pintype "bidirectional"))
      (node (ref "MSP1") (pin "79") (pinfunction "AVCC1_79") (pintype "bidirectional"))
      (node (ref "MSP1") (pin "99") (pinfunction "DVCC3_99") (pintype "bidirectional"))
      (node (ref "R11") (pin "2") (pinfunction "2_2") (pintype "passive"))
      (node (ref "R16") (pin "2") (pinfunction "2_2") (pintype "passive"))
      (node (ref "R17") (pin "2") (pinfunction "2_2") (pintype "passive"))
      (node (ref "R3") (pin "1") (pinfunction "1_1") (pintype "passive"))
      (node (ref "R8") (pin "1") (pinfunction "1_1") (pintype "passive"))
      (node (ref "R9") (pin "1") (pinfunction "1_1") (pintype "passive"))
      (node (ref "S1") (pin "2") (pinfunction "P_2") (pintype "passive"))
      (node (ref "U3") (pin "13") (pinfunction "VCC_13") (pintype "bidirectional"))
      (node (ref "U4") (pin "1") (pinfunction "VIN_1") (pintype "bidirectional"))
    )
    (net (code "69") (name "VIN") (class "Default")
      (node (ref "J2") (pin "4") (pinfunction "ICSP_DAT/PGD_4") (pintype "bidirectional"))
      (node (ref "R22") (pin "1") (pinfunction "1_1") (pintype "passive"))
      (node (ref "R24") (pin "1") (pinfunction "1_1") (pintype "passive"))
      (node (ref "U1") (pin "1") (pinfunction "CE_1") (pintype "bidirectional"))
      (node (ref "U1") (pin "4") (pinfunction "VIN_4") (pintype "bidirectional"))
      (node (ref "U10") (pin "8") (pinfunction "VCC+_8") (pintype "bidirectional"))
      (node (ref "U2") (pin "4") (pinfunction "OUT_4") (pintype "bidirectional"))
      (node (ref "U5") (pin "1") (pinfunction "VDD_1") (pintype "bidirectional"))
      (node (ref "U7") (pin "8") (pinfunction "VCC+_8") (pintype "bidirectional"))
      (node (ref "U8") (pin "1") (pinfunction "VDD_1") (pintype "bidirectional"))
    )
    (net (code "70") (name "WP_CTRL_ECHO") (class "Default")
      (node (ref "MSP1") (pin "14") (pinfunction "P2.4/TB0.3/COM4/S43_14") (pintype "bidirectional"))
      (node (ref "U5") (pin "9") (pinfunction "WP_9") (pintype "bidirectional"))
    )
    (net (code "71") (name "WP_CTRL_RADIO") (class "Default")
      (node (ref "MSP1") (pin "11") (pinfunction "P6.4/TB0.0/COM1_11") (pintype "bidirectional"))
      (node (ref "U8") (pin "9") (pinfunction "WP_9") (pintype "bidirectional"))
    )
    (net (code "72") (name "unconnected-(MSP1-ESICI-Pad77)") (class "Default")
      (node (ref "MSP1") (pin "77") (pinfunction "ESICI_77") (pintype "bidirectional"))
    )
    (net (code "73") (name "unconnected-(MSP1-ESICOM-Pad78)") (class "Default")
      (node (ref "MSP1") (pin "78") (pinfunction "ESICOM_78") (pintype "bidirectional"))
    )
    (net (code "74") (name "unconnected-(MSP1-ESIVCC-Pad75)") (class "Default")
      (node (ref "MSP1") (pin "75") (pinfunction "ESIVCC_75") (pintype "bidirectional"))
    )
    (net (code "75") (name "unconnected-(MSP1-ESIVSS-Pad76)") (class "Default")
      (node (ref "MSP1") (pin "76") (pinfunction "ESIVSS_76") (pintype "bidirectional"))
    )
    (net (code "76") (name "unconnected-(MSP1-P1.1{slash}TA0.2{slash}TA1CLK{slash}COUT{slash}A1{slash}C1{slash}VREF+{slash}VEREF+-Pad65)") (class "Default")
      (node (ref "MSP1") (pin "65") (pinfunction "P1.1/TA0.2/TA1CLK/COUT/A1/C1/VREF+/VEREF+_65") (pintype "bidirectional"))
    )
    (net (code "77") (name "unconnected-(MSP1-P1.2{slash}TA1.1{slash}TA0CLK{slash}COUT{slash}A2{slash}C2-Pad64)") (class "Default")
      (node (ref "MSP1") (pin "64") (pinfunction "P1.2/TA1.1/TA0CLK/COUT/A2/C2_64") (pintype "bidirectional"))
    )
    (net (code "78") (name "unconnected-(MSP1-P1.3{slash}TA1.2{slash}ESITEST4{slash}A3{slash}C3-Pad63)") (class "Default")
      (node (ref "MSP1") (pin "63") (pinfunction "P1.3/TA1.2/ESITEST4/A3/C3_63") (pintype "bidirectional"))
    )
    (net (code "79") (name "unconnected-(MSP1-P2.1{slash}UCA0SOMI{slash}UCA0RXD{slash}TB0.5{slash}DMAE0-Pad50)") (class "Default")
      (node (ref "MSP1") (pin "50") (pinfunction "P2.1/UCA0SOMI/UCA0RXD/TB0.5/DMAE0_50") (pintype "bidirectional"))
    )
    (net (code "80") (name "unconnected-(MSP1-P2.2{slash}UCA0CLK{slash}TB0.4{slash}RTCCLK-Pad49)") (class "Default")
      (node (ref "MSP1") (pin "49") (pinfunction "P2.2/UCA0CLK/TB0.4/RTCCLK_49") (pintype "bidirectional"))
    )
    (net (code "81") (name "unconnected-(MSP1-P2.3{slash}UCA0STE{slash}TB0OUTH-Pad48)") (class "Default")
      (node (ref "MSP1") (pin "48") (pinfunction "P2.3/UCA0STE/TB0OUTH_48") (pintype "bidirectional"))
    )
    (net (code "82") (name "unconnected-(MSP1-P2.5{slash}TB0.4{slash}COM5{slash}S42-Pad15)") (class "Default")
      (node (ref "MSP1") (pin "15") (pinfunction "P2.5/TB0.4/COM5/S42_15") (pintype "bidirectional"))
    )
    (net (code "83") (name "unconnected-(MSP1-P2.6{slash}TB0.5{slash}ESIC1OUT{slash}COM6{slash}S41-Pad16)") (class "Default")
      (node (ref "MSP1") (pin "16") (pinfunction "P2.6/TB0.5/ESIC1OUT/COM6/S41_16") (pintype "bidirectional"))
    )
    (net (code "84") (name "unconnected-(MSP1-P2.7{slash}TB0.6{slash}ESIC2OUT{slash}COM7{slash}S40-Pad17)") (class "Default")
      (node (ref "MSP1") (pin "17") (pinfunction "P2.7/TB0.6/ESIC2OUT/COM7/S40_17") (pintype "bidirectional"))
    )
    (net (code "85") (name "unconnected-(MSP1-P3.0{slash}UCB1CLK{slash}S34-Pad23)") (class "Default")
      (node (ref "MSP1") (pin "23") (pinfunction "P3.0/UCB1CLK/S34_23") (pintype "bidirectional"))
    )
    (net (code "86") (name "unconnected-(MSP1-P3.3{slash}TA1.1{slash}TB0CLK{slash}S26-Pad39)") (class "Default")
      (node (ref "MSP1") (pin "39") (pinfunction "P3.3/TA1.1/TB0CLK/S26_39") (pintype "bidirectional"))
    )
    (net (code "87") (name "unconnected-(MSP1-P3.4{slash}UCA1SIMO{slash}UCA1TXD{slash}TB0.0{slash}S25-Pad40)") (class "Default")
      (node (ref "MSP1") (pin "40") (pinfunction "P3.4/UCA1SIMO/UCA1TXD/TB0.0/S25_40") (pintype "bidirectional"))
    )
    (net (code "88") (name "unconnected-(MSP1-P3.5{slash}UCA1SOMI{slash}UCA1RXD{slash}TB0.1{slash}S24-Pad41)") (class "Default")
      (node (ref "MSP1") (pin "41") (pinfunction "P3.5/UCA1SOMI/UCA1RXD/TB0.1/S24_41") (pintype "bidirectional"))
    )
    (net (code "89") (name "unconnected-(MSP1-P3.6{slash}UCA1CLK{slash}TB0.2{slash}S23-Pad42)") (class "Default")
      (node (ref "MSP1") (pin "42") (pinfunction "P3.6/UCA1CLK/TB0.2/S23_42") (pintype "bidirectional"))
    )
    (net (code "90") (name "unconnected-(MSP1-P3.7{slash}UCA1STE{slash}TB0.3{slash}S22-Pad43)") (class "Default")
      (node (ref "MSP1") (pin "43") (pinfunction "P3.7/UCA1STE/TB0.3/S22_43") (pintype "bidirectional"))
    )
    (net (code "91") (name "unconnected-(MSP1-P4.0{slash}UCB1SIMO{slash}UCB1SDA{slash}MCLK{slash}S3-Pad96)") (class "Default")
      (node (ref "MSP1") (pin "96") (pinfunction "P4.0/UCB1SIMO/UCB1SDA/MCLK/S3_96") (pintype "bidirectional"))
    )
    (net (code "92") (name "unconnected-(MSP1-P4.1{slash}UCB1SOMI{slash}UCB1SCL{slash}ACLK{slash}S2-Pad97)") (class "Default")
      (node (ref "MSP1") (pin "97") (pinfunction "P4.1/UCB1SOMI/UCB1SCL/ACLK/S2_97") (pintype "bidirectional"))
    )
    (net (code "93") (name "unconnected-(MSP1-P4.2{slash}UCA0SIMO{slash}UCA0TXD{slash}UCB1CLK-Pad100)") (class "Default")
      (node (ref "MSP1") (pin "100") (pinfunction "P4.2/UCA0SIMO/UCA0TXD/UCB1CLK_100") (pintype "bidirectional"))
    )
    (net (code "94") (name "unconnected-(MSP1-P4.3{slash}UCA0SOMI{slash}UCA0RXD{slash}UCB1STE-Pad1)") (class "Default")
      (node (ref "MSP1") (pin "1") (pinfunction "P4.3/UCA0SOMI/UCA0RXD/UCB1STE_1") (pintype "bidirectional"))
    )
    (net (code "95") (name "unconnected-(MSP1-P4.4{slash}UCB1STE{slash}TA1CLK{slash}S8-Pad91)") (class "Default")
      (node (ref "MSP1") (pin "91") (pinfunction "P4.4/UCB1STE/TA1CLK/S8_91") (pintype "bidirectional"))
    )
    (net (code "96") (name "unconnected-(MSP1-P4.5{slash}UCB1CLK{slash}TA1.0{slash}S7-Pad92)") (class "Default")
      (node (ref "MSP1") (pin "92") (pinfunction "P4.5/UCB1CLK/TA1.0/S7_92") (pintype "bidirectional"))
    )
    (net (code "97") (name "unconnected-(MSP1-P4.6{slash}UCB1SIMO{slash}UCB1SDA{slash}TA1.1{slash}S6-Pad93)") (class "Default")
      (node (ref "MSP1") (pin "93") (pinfunction "P4.6/UCB1SIMO/UCB1SDA/TA1.1/S6_93") (pintype "bidirectional"))
    )
    (net (code "98") (name "unconnected-(MSP1-P4.7{slash}UCB1SOMI{slash}UCB1SCL{slash}TA1.2{slash}S5-Pad94)") (class "Default")
      (node (ref "MSP1") (pin "94") (pinfunction "P4.7/UCB1SOMI/UCB1SCL/TA1.2/S5_94") (pintype "bidirectional"))
    )
    (net (code "99") (name "unconnected-(MSP1-P5.1{slash}TA1.2{slash}S37-Pad20)") (class "Default")
      (node (ref "MSP1") (pin "20") (pinfunction "P5.1/TA1.2/S37_20") (pintype "bidirectional"))
    )
    (net (code "100") (name "unconnected-(MSP1-P5.4{slash}UCA1SIMO{slash}UCA1TXD{slash}S12-Pad87)") (class "Default")
      (node (ref "MSP1") (pin "87") (pinfunction "P5.4/UCA1SIMO/UCA1TXD/S12_87") (pintype "bidirectional"))
    )
    (net (code "101") (name "unconnected-(MSP1-P5.5{slash}UCA1SOMI{slash}UCA1RXD{slash}S11-Pad88)") (class "Default")
      (node (ref "MSP1") (pin "88") (pinfunction "P5.5/UCA1SOMI/UCA1RXD/S11_88") (pintype "bidirectional"))
    )
    (net (code "102") (name "unconnected-(MSP1-P5.6{slash}UCA1CLK{slash}S10-Pad89)") (class "Default")
      (node (ref "MSP1") (pin "89") (pinfunction "P5.6/UCA1CLK/S10_89") (pintype "bidirectional"))
    )
    (net (code "103") (name "unconnected-(MSP1-P5.7{slash}UCA1STE{slash}TB0CLK{slash}S9-Pad90)") (class "Default")
      (node (ref "MSP1") (pin "90") (pinfunction "P5.7/UCA1STE/TB0CLK/S9_90") (pintype "bidirectional"))
    )
    (net (code "104") (name "unconnected-(MSP1-P6.7{slash}TA0CLK{slash}S31-Pad34)") (class "Default")
      (node (ref "MSP1") (pin "34") (pinfunction "P6.7/TA0CLK/S31_34") (pintype "bidirectional"))
    )
    (net (code "105") (name "unconnected-(MSP1-P7.5{slash}TA0.2{slash}S30-Pad35)") (class "Default")
      (node (ref "MSP1") (pin "35") (pinfunction "P7.5/TA0.2/S30_35") (pintype "bidirectional"))
    )
    (net (code "106") (name "unconnected-(MSP1-P7.6{slash}TA0.1{slash}S29-Pad36)") (class "Default")
      (node (ref "MSP1") (pin "36") (pinfunction "P7.6/TA0.1/S29_36") (pintype "bidirectional"))
    )
    (net (code "107") (name "unconnected-(MSP1-P7.7{slash}TA1.2{slash}TB0OUTH{slash}S27-Pad38)") (class "Default")
      (node (ref "MSP1") (pin "38") (pinfunction "P7.7/TA1.2/TB0OUTH/S27_38") (pintype "bidirectional"))
    )
    (net (code "108") (name "unconnected-(MSP1-P8.0{slash}RTCCLK{slash}S21-Pad44)") (class "Default")
      (node (ref "MSP1") (pin "44") (pinfunction "P8.0/RTCCLK/S21_44") (pintype "bidirectional"))
    )
    (net (code "109") (name "unconnected-(MSP1-P8.1{slash}DMAE0{slash}S20-Pad45)") (class "Default")
      (node (ref "MSP1") (pin "45") (pinfunction "P8.1/DMAE0/S20_45") (pintype "bidirectional"))
    )
    (net (code "110") (name "unconnected-(MSP1-P8.2{slash}S19-Pad46)") (class "Default")
      (node (ref "MSP1") (pin "46") (pinfunction "P8.2/S19_46") (pintype "bidirectional"))
    )
    (net (code "111") (name "unconnected-(MSP1-P8.3{slash}MCLK{slash}S18-Pad47)") (class "Default")
      (node (ref "MSP1") (pin "47") (pinfunction "P8.3/MCLK/S18_47") (pintype "bidirectional"))
    )
    (net (code "112") (name "unconnected-(MSP1-P8.4{slash}A7{slash}C7-Pad59)") (class "Default")
      (node (ref "MSP1") (pin "59") (pinfunction "P8.4/A7/C7_59") (pintype "bidirectional"))
    )
    (net (code "113") (name "unconnected-(MSP1-P8.5{slash}A6{slash}C6-Pad60)") (class "Default")
      (node (ref "MSP1") (pin "60") (pinfunction "P8.5/A6/C6_60") (pintype "bidirectional"))
    )
    (net (code "114") (name "unconnected-(MSP1-P8.6{slash}A5{slash}C5-Pad61)") (class "Default")
      (node (ref "MSP1") (pin "61") (pinfunction "P8.6/A5/C5_61") (pintype "bidirectional"))
    )
    (net (code "115") (name "unconnected-(MSP1-P8.7{slash}A4{slash}C4-Pad62)") (class "Default")
      (node (ref "MSP1") (pin "62") (pinfunction "P8.7/A4/C4_62") (pintype "bidirectional"))
    )
    (net (code "116") (name "unconnected-(MSP1-P9.0{slash}ESICH0{slash}ESITEST0{slash}A8{slash}C8-Pad67)") (class "Default")
      (node (ref "MSP1") (pin "67") (pinfunction "P9.0/ESICH0/ESITEST0/A8/C8_67") (pintype "bidirectional"))
    )
    (net (code "117") (name "unconnected-(MSP1-P9.1{slash}ESICH1{slash}ESITEST1{slash}A9{slash}C9-Pad68)") (class "Default")
      (node (ref "MSP1") (pin "68") (pinfunction "P9.1/ESICH1/ESITEST1/A9/C9_68") (pintype "bidirectional"))
    )
    (net (code "118") (name "unconnected-(MSP1-P9.3{slash}ESICH3{slash}ESITEST3{slash}A11{slash}C11-Pad70)") (class "Default")
      (node (ref "MSP1") (pin "70") (pinfunction "P9.3/ESICH3/ESITEST3/A11/C11_70") (pintype "bidirectional"))
    )
    (net (code "119") (name "unconnected-(MSP1-P10.0{slash}SMCLK{slash}S4-Pad95)") (class "Default")
      (node (ref "MSP1") (pin "95") (pinfunction "P10.0/SMCLK/S4_95") (pintype "bidirectional"))
    )
    (net (code "120") (name "unconnected-(MSP1-P10.1{slash}TA0.0{slash}S28-Pad37)") (class "Default")
      (node (ref "MSP1") (pin "37") (pinfunction "P10.1/TA0.0/S28_37") (pintype "bidirectional"))
    )
    (net (code "121") (name "unconnected-(MSP1-PJ.0{slash}TDO{slash}TB0OUTH{slash}SMCLK{slash}SRSCG1-Pad30)") (class "Default")
      (node (ref "MSP1") (pin "30") (pinfunction "PJ.0/TDO/TB0OUTH/SMCLK/SRSCG1_30") (pintype "bidirectional"))
    )
    (net (code "122") (name "unconnected-(MSP1-PJ.1{slash}TDI{slash}TCLK{slash}MCLK{slash}SRSCG-Pad31)") (class "Default")
      (node (ref "MSP1") (pin "31") (pinfunction "PJ.1/TDI/TCLK/MCLK/SRSCG_31") (pintype "bidirectional"))
    )
    (net (code "123") (name "unconnected-(MSP1-PJ.2{slash}TMS{slash}ACLK{slash}SROSCOFF-Pad32)") (class "Default")
      (node (ref "MSP1") (pin "32") (pinfunction "PJ.2/TMS/ACLK/SROSCOFF_32") (pintype "bidirectional"))
    )
    (net (code "124") (name "unconnected-(MSP1-PJ.3{slash}TCK{slash}COUT{slash}SRCPUOFF-Pad33)") (class "Default")
      (node (ref "MSP1") (pin "33") (pinfunction "PJ.3/TCK/COUT/SRCPUOFF_33") (pintype "bidirectional"))
    )
    (net (code "125") (name "unconnected-(MSP1-PJ.4{slash}LFXIN-Pad84)") (class "Default")
      (node (ref "MSP1") (pin "84") (pinfunction "PJ.4/LFXIN_84") (pintype "bidirectional"))
    )
    (net (code "126") (name "unconnected-(MSP1-PJ.5{slash}LFXOUT-Pad85)") (class "Default")
      (node (ref "MSP1") (pin "85") (pinfunction "PJ.5/LFXOUT_85") (pintype "bidirectional"))
    )
    (net (code "127") (name "unconnected-(MSP1-PJ.6{slash}HFXIN-Pad82)") (class "Default")
      (node (ref "MSP1") (pin "82") (pinfunction "PJ.6/HFXIN_82") (pintype "bidirectional"))
    )
    (net (code "128") (name "unconnected-(MSP1-PJ.7{slash}HFXOUT-Pad81)") (class "Default")
      (node (ref "MSP1") (pin "81") (pinfunction "PJ.7/HFXOUT_81") (pintype "bidirectional"))
    )
    (net (code "129") (name "unconnected-(MSP1-R33{slash}LCDCAP-Pad6)") (class "Default")
      (node (ref "MSP1") (pin "6") (pinfunction "R33/LCDCAP_6") (pintype "bidirectional"))
    )
    (net (code "130") (name "unconnected-(U3-AF-Pad14)") (class "Default")
      (node (ref "U3") (pin "14") (pinfunction "AF_14") (pintype "bidirectional"))
    )
    (net (code "131") (name "unconnected-(U3-FOUT{slash}IRQ-Pad11)") (class "Default")
      (node (ref "U3") (pin "11") (pinfunction "FOUT/IRQ_11") (pintype "bidirectional"))
    )
    (net (code "132") (name "unconnected-(U3-IRQ2-Pad4)") (class "Default")
      (node (ref "U3") (pin "4") (pinfunction "IRQ2_4") (pintype "bidirectional"))
    )
    (net (code "133") (name "unconnected-(U3-TIRQ-Pad12)") (class "Default")
      (node (ref "U3") (pin "12") (pinfunction "TIRQ_12") (pintype "bidirectional"))
    )
    (net (code "134") (name "unconnected-(U3-XI-Pad16)") (class "Default")
      (node (ref "U3") (pin "16") (pinfunction "XI_16") (pintype "bidirectional"))
    )
    (net (code "135") (name "unconnected-(U3-XO-Pad15)") (class "Default")
      (node (ref "U3") (pin "15") (pinfunction "XO_15") (pintype "bidirectional"))
    )
    (net (code "136") (name "unconnected-(U5-HA-Pad15)") (class "Default")
      (node (ref "U5") (pin "15") (pinfunction "HA_15") (pintype "passive"))
    )
    (net (code "137") (name "unconnected-(U5-HB-Pad12)") (class "Default")
      (node (ref "U5") (pin "12") (pinfunction "HB_12") (pintype "bidirectional"))
    )
    (net (code "138") (name "unconnected-(U8-HA-Pad15)") (class "Default")
      (node (ref "U8") (pin "15") (pinfunction "HA_15") (pintype "passive"))
    )
    (net (code "139") (name "unconnected-(U8-HB-Pad12)") (class "Default")
      (node (ref "U8") (pin "12") (pinfunction "HB_12") (pintype "bidirectional"))
    )
  )
)
